# CP2102_USB_to_Serial_Breakout.net
KiCad netlist of a schematic drawn in EAGLE
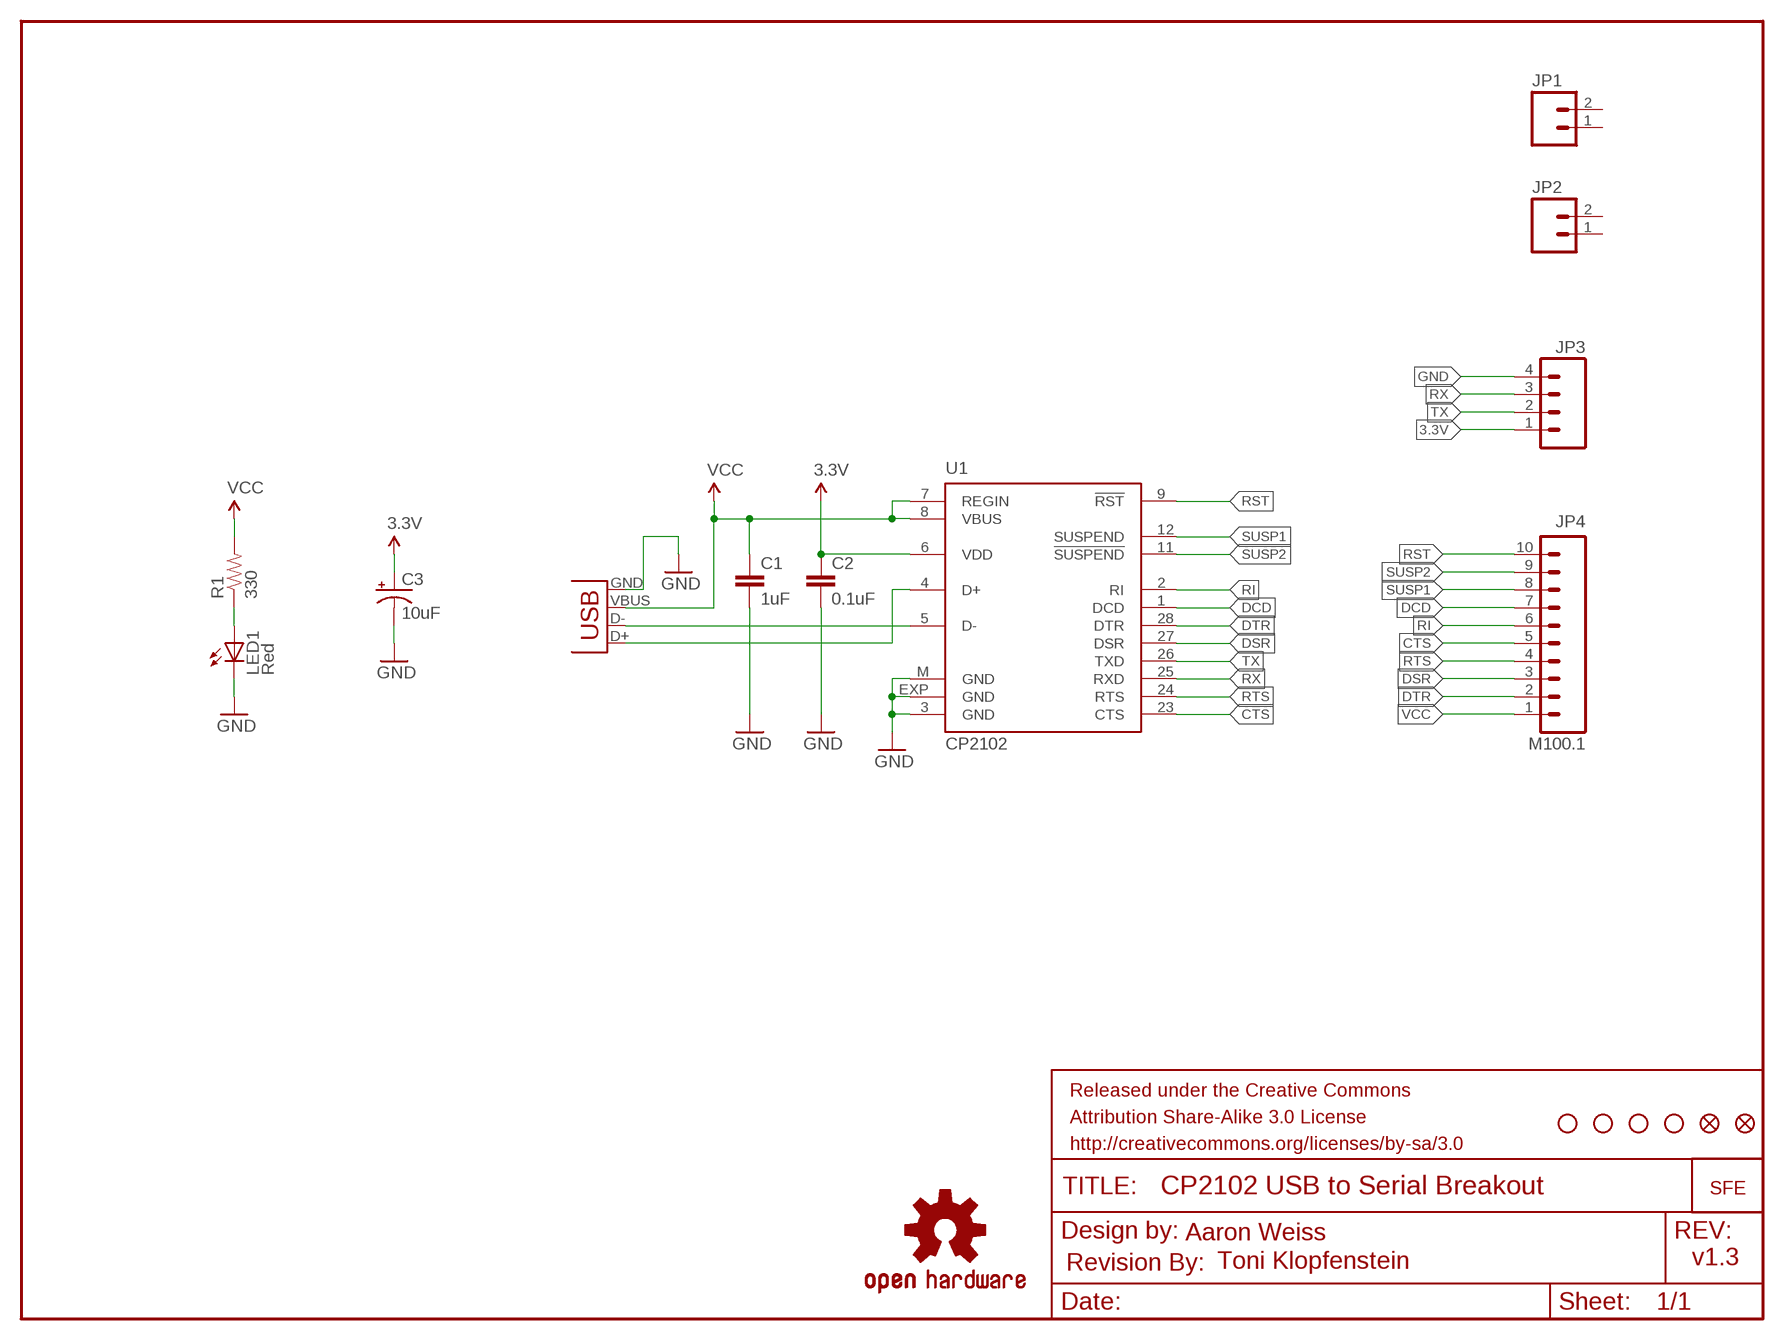
[diagram p0: schematic, sheet 1]

(export (version "E")
  (design (tool "Eeschema 10.0.6"))
  (components
    (comp (ref "C1")
      (value "1uF")
      (footprint "eagle-import:0603-CAP")
      (libsource (lib "eagle-import") (part "1.0UF-16V-10%(0603)"))
    )
    (comp (ref "C2")
      (value "0.1uF")
      (footprint "eagle-import:0603-CAP")
      (libsource (lib "eagle-import") (part "0.1UF-25V(+80/-20%)(0603)"))
    )
    (comp (ref "C3")
      (value "10uF")
      (footprint "eagle-import:EIA3216")
      (libsource (lib "eagle-import") (part "CAP_POL1206"))
    )
    (comp (ref "FID1")
      (value "FIDUCIAL1X2")
      (footprint "eagle-import:FIDUCIAL-1X2")
      (libsource (lib "eagle-import") (part "FIDUCIAL1X2"))
    )
    (comp (ref "FID2")
      (value "FIDUCIAL1X2")
      (footprint "eagle-import:FIDUCIAL-1X2")
      (libsource (lib "eagle-import") (part "FIDUCIAL1X2"))
    )
    (comp (ref "FRAME1")
      (value "FRAME-LETTER")
      (footprint "eagle-import:CREATIVE_COMMONS")
      (libsource (lib "eagle-import") (part "FRAME-LETTER"))
    )
    (comp (ref "JP1")
      (value "M02PTH")
      (footprint "eagle-import:1X02")
      (libsource (lib "eagle-import") (part "M02PTH"))
    )
    (comp (ref "JP2")
      (value "M02PTH")
      (footprint "eagle-import:1X02")
      (libsource (lib "eagle-import") (part "M02PTH"))
    )
    (comp (ref "JP3")
      (value "M04PTH")
      (footprint "eagle-import:1X04")
      (libsource (lib "eagle-import") (part "M04PTH"))
    )
    (comp (ref "JP4")
      (value "M100.1")
      (footprint "eagle-import:1X10")
      (libsource (lib "eagle-import") (part "M100.1"))
    )
    (comp (ref "LED1")
      (value "Red")
      (footprint "eagle-import:LED-1206")
      (libsource (lib "eagle-import") (part "LED1206"))
    )
    (comp (ref "LOGO1")
      (value "OSHW-LOGOS")
      (footprint "eagle-import:OSHW-LOGO-S")
      (libsource (lib "eagle-import") (part "OSHW-LOGOS"))
    )
    (comp (ref "R1")
      (value "330")
      (footprint "eagle-import:0603-RES")
      (libsource (lib "eagle-import") (part "330OHM1/10W1%(0603)"))
    )
    (comp (ref "U$1")
      (value "LOGO-SFENEW")
      (footprint "eagle-import:SFE-NEW-WEBLOGO")
      (libsource (lib "eagle-import") (part "LOGO-SFENEW"))
    )
    (comp (ref "U$4")
      (value "REVISION")
      (footprint "eagle-import:REVISION")
      (libsource (lib "eagle-import") (part "REVISION"))
    )
    (comp (ref "U$6")
      (value "STAND-OFF")
      (footprint "eagle-import:STAND-OFF")
      (libsource (lib "eagle-import") (part "STAND-OFF"))
    )
    (comp (ref "U$7")
      (value "STAND-OFF")
      (footprint "eagle-import:STAND-OFF")
      (libsource (lib "eagle-import") (part "STAND-OFF"))
    )
    (comp (ref "U$8")
      (value "STAND-OFF")
      (footprint "eagle-import:STAND-OFF")
      (libsource (lib "eagle-import") (part "STAND-OFF"))
    )
    (comp (ref "U$9")
      (value "STAND-OFF")
      (footprint "eagle-import:STAND-OFF")
      (libsource (lib "eagle-import") (part "STAND-OFF"))
    )
    (comp (ref "U1")
      (value "CP2102")
      (footprint "eagle-import:MLP28")
      (libsource (lib "eagle-import") (part "CP210X_USB_UART"))
    )
    (comp (ref "X1")
      (value "USBPTH")
      (footprint "eagle-import:USB-B-PTH")
      (libsource (lib "eagle-import") (part "USBPTH"))
    )
  )
  (nets
    (net (code "1") (name "3.3V") (class "Default")
      (node (ref "C2") (pin "1") (pinfunction "1_1") (pintype "passive"))
      (node (ref "C3") (pin "A") (pinfunction "+_A") (pintype "passive"))
      (node (ref "JP3") (pin "1") (pinfunction "1_1") (pintype "passive"))
      (node (ref "U1") (pin "6") (pinfunction "VDD_6") (pintype "power_in"))
    )
    (net (code "2") (name "CTS") (class "Default")
      (node (ref "JP4") (pin "5") (pinfunction "5_5") (pintype "passive"))
      (node (ref "U1") (pin "23") (pinfunction "CTS_23") (pintype "input"))
    )
    (net (code "3") (name "DCD") (class "Default")
      (node (ref "JP4") (pin "7") (pinfunction "7_7") (pintype "passive"))
      (node (ref "U1") (pin "1") (pinfunction "DCD_1") (pintype "input"))
    )
    (net (code "4") (name "DSR") (class "Default")
      (node (ref "JP4") (pin "3") (pinfunction "3_3") (pintype "passive"))
      (node (ref "U1") (pin "27") (pinfunction "DSR_27") (pintype "input"))
    )
    (net (code "5") (name "DTR") (class "Default")
      (node (ref "JP4") (pin "2") (pinfunction "2_2") (pintype "passive"))
      (node (ref "U1") (pin "28") (pinfunction "DTR_28") (pintype "output"))
    )
    (net (code "6") (name "GND") (class "Default")
      (node (ref "C1") (pin "2") (pinfunction "2_2") (pintype "passive"))
      (node (ref "C2") (pin "2") (pinfunction "2_2") (pintype "passive"))
      (node (ref "C3") (pin "C") (pinfunction "-_C") (pintype "passive"))
      (node (ref "JP3") (pin "4") (pinfunction "4_4") (pintype "passive"))
      (node (ref "LED1") (pin "C") (pinfunction "C_C") (pintype "passive"))
      (node (ref "U1") (pin "3") (pinfunction "GND_3") (pintype "power_in"))
      (node (ref "U1") (pin "EXP") (pinfunction "GND_EXP") (pintype "power_in"))
      (node (ref "U1") (pin "M") (pinfunction "GND_M") (pintype "power_in"))
      (node (ref "X1") (pin "GND") (pinfunction "GND_GND") (pintype "bidirectional"))
    )
    (net (code "7") (name "Net-(LED1-PadA)") (class "Default")
      (node (ref "LED1") (pin "A") (pinfunction "A_A") (pintype "passive"))
      (node (ref "R1") (pin "1") (pinfunction "1_1") (pintype "passive"))
    )
    (net (code "8") (name "Net-(U1-D+)") (class "Default")
      (node (ref "U1") (pin "4") (pinfunction "D+_4") (pintype "bidirectional"))
      (node (ref "X1") (pin "D+") (pinfunction "D+_D+") (pintype "bidirectional"))
    )
    (net (code "9") (name "Net-(U1-D-)") (class "Default")
      (node (ref "U1") (pin "5") (pinfunction "D-_5") (pintype "bidirectional"))
      (node (ref "X1") (pin "D-") (pinfunction "D-_D-") (pintype "bidirectional"))
    )
    (net (code "10") (name "RI") (class "Default")
      (node (ref "JP4") (pin "6") (pinfunction "6_6") (pintype "passive"))
      (node (ref "U1") (pin "2") (pinfunction "RI_2") (pintype "input"))
    )
    (net (code "11") (name "RST") (class "Default")
      (node (ref "JP4") (pin "10") (pinfunction "10_10") (pintype "passive"))
      (node (ref "U1") (pin "9") (pinfunction "~{RST}_9") (pintype "bidirectional"))
    )
    (net (code "12") (name "RTS") (class "Default")
      (node (ref "JP4") (pin "4") (pinfunction "4_4") (pintype "passive"))
      (node (ref "U1") (pin "24") (pinfunction "RTS_24") (pintype "output"))
    )
    (net (code "13") (name "RX") (class "Default")
      (node (ref "JP3") (pin "3") (pinfunction "3_3") (pintype "passive"))
      (node (ref "U1") (pin "25") (pinfunction "RXD_25") (pintype "input"))
    )
    (net (code "14") (name "SUSP1") (class "Default")
      (node (ref "JP4") (pin "8") (pinfunction "8_8") (pintype "passive"))
      (node (ref "U1") (pin "12") (pinfunction "SUSPEND_12") (pintype "output"))
    )
    (net (code "15") (name "SUSP2") (class "Default")
      (node (ref "JP4") (pin "9") (pinfunction "9_9") (pintype "passive"))
      (node (ref "U1") (pin "11") (pinfunction "~{SUSPEND}_11") (pintype "output"))
    )
    (net (code "16") (name "TX") (class "Default")
      (node (ref "JP3") (pin "2") (pinfunction "2_2") (pintype "passive"))
      (node (ref "U1") (pin "26") (pinfunction "TXD_26") (pintype "output"))
    )
    (net (code "17") (name "VCC") (class "Default")
      (node (ref "C1") (pin "1") (pinfunction "1_1") (pintype "passive"))
      (node (ref "JP4") (pin "1") (pinfunction "1_1") (pintype "passive"))
      (node (ref "R1") (pin "2") (pinfunction "2_2") (pintype "passive"))
      (node (ref "U1") (pin "7") (pinfunction "REGIN_7") (pintype "passive"))
      (node (ref "U1") (pin "8") (pinfunction "VBUS_8") (pintype "input"))
      (node (ref "X1") (pin "VBUS") (pinfunction "VBUS_VBUS") (pintype "bidirectional"))
    )
    (net (code "18") (name "unconnected-(JP1-Pad1)") (class "Default")
      (node (ref "JP1") (pin "1") (pinfunction "1_1") (pintype "passive"))
    )
    (net (code "19") (name "unconnected-(JP1-Pad2)") (class "Default")
      (node (ref "JP1") (pin "2") (pinfunction "2_2") (pintype "passive"))
    )
    (net (code "20") (name "unconnected-(JP2-Pad1)") (class "Default")
      (node (ref "JP2") (pin "1") (pinfunction "1_1") (pintype "passive"))
    )
    (net (code "21") (name "unconnected-(JP2-Pad2)") (class "Default")
      (node (ref "JP2") (pin "2") (pinfunction "2_2") (pintype "passive"))
    )
  )
)
